# 12_MSM8916_POWER3.net
KiCad netlist of a schematic drawn in Altium Designer
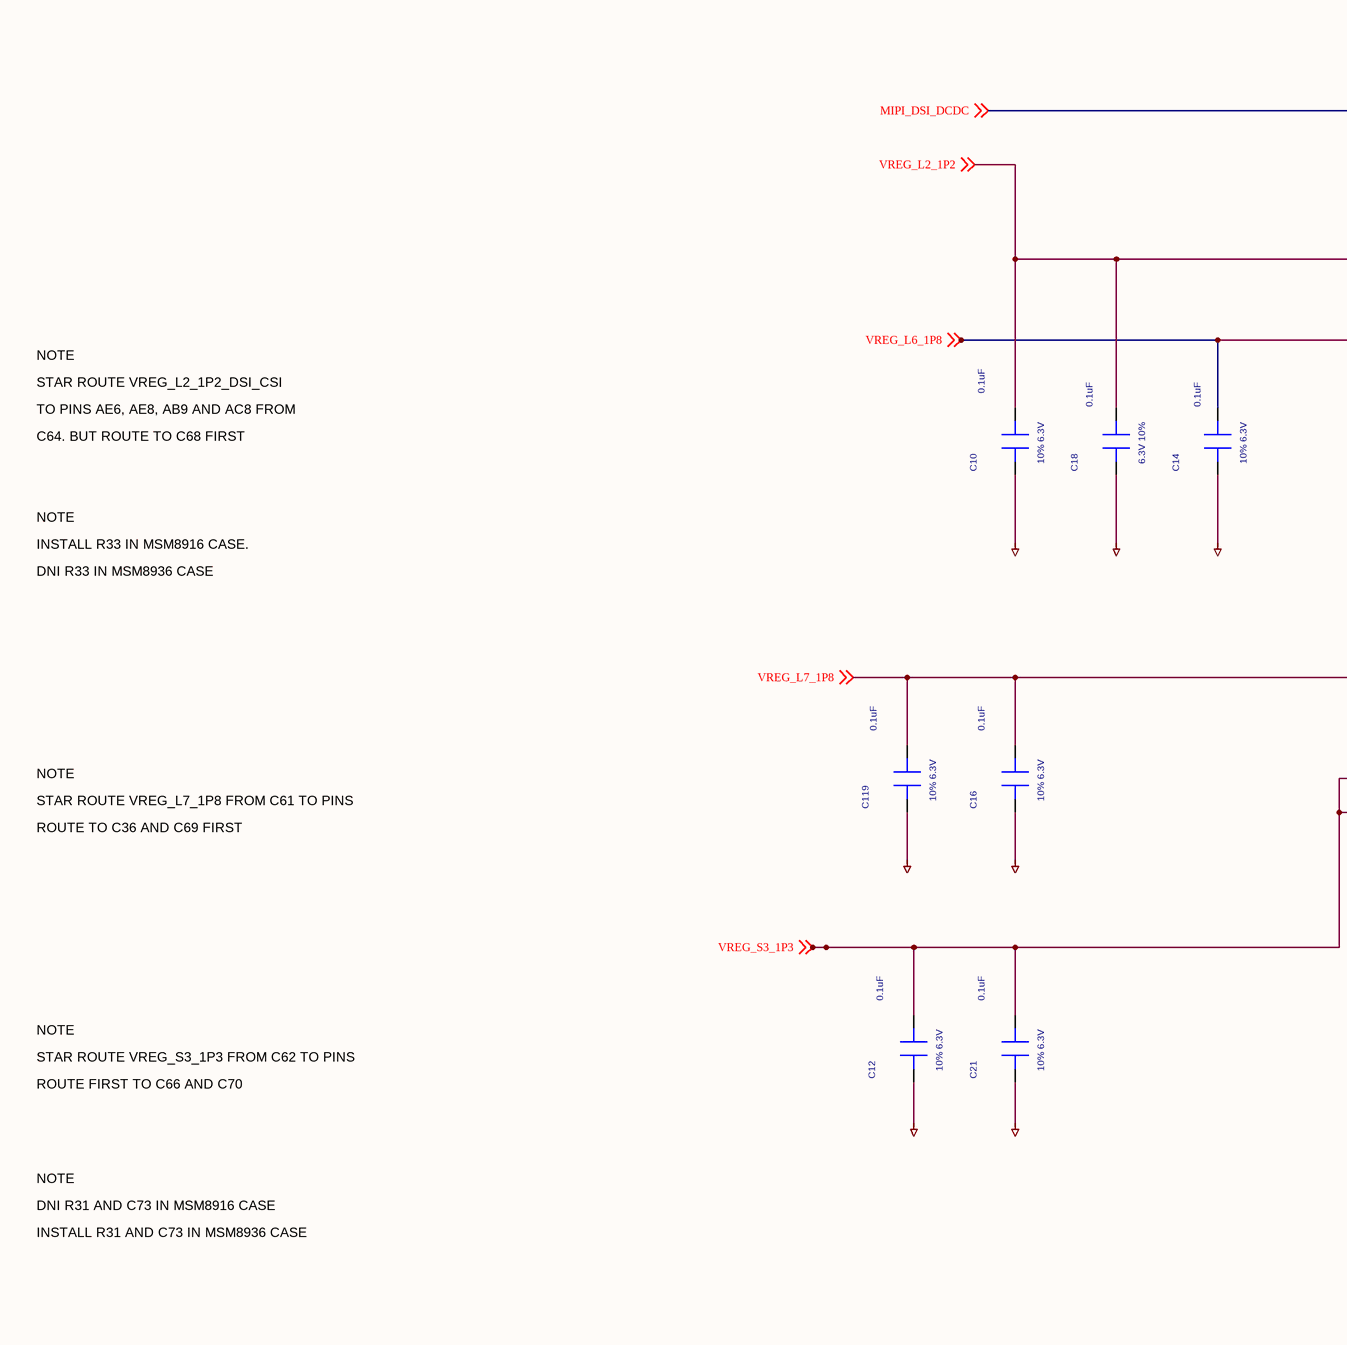
[diagram p0: 12 MSM8916_POWER3.SchDoc, top left]
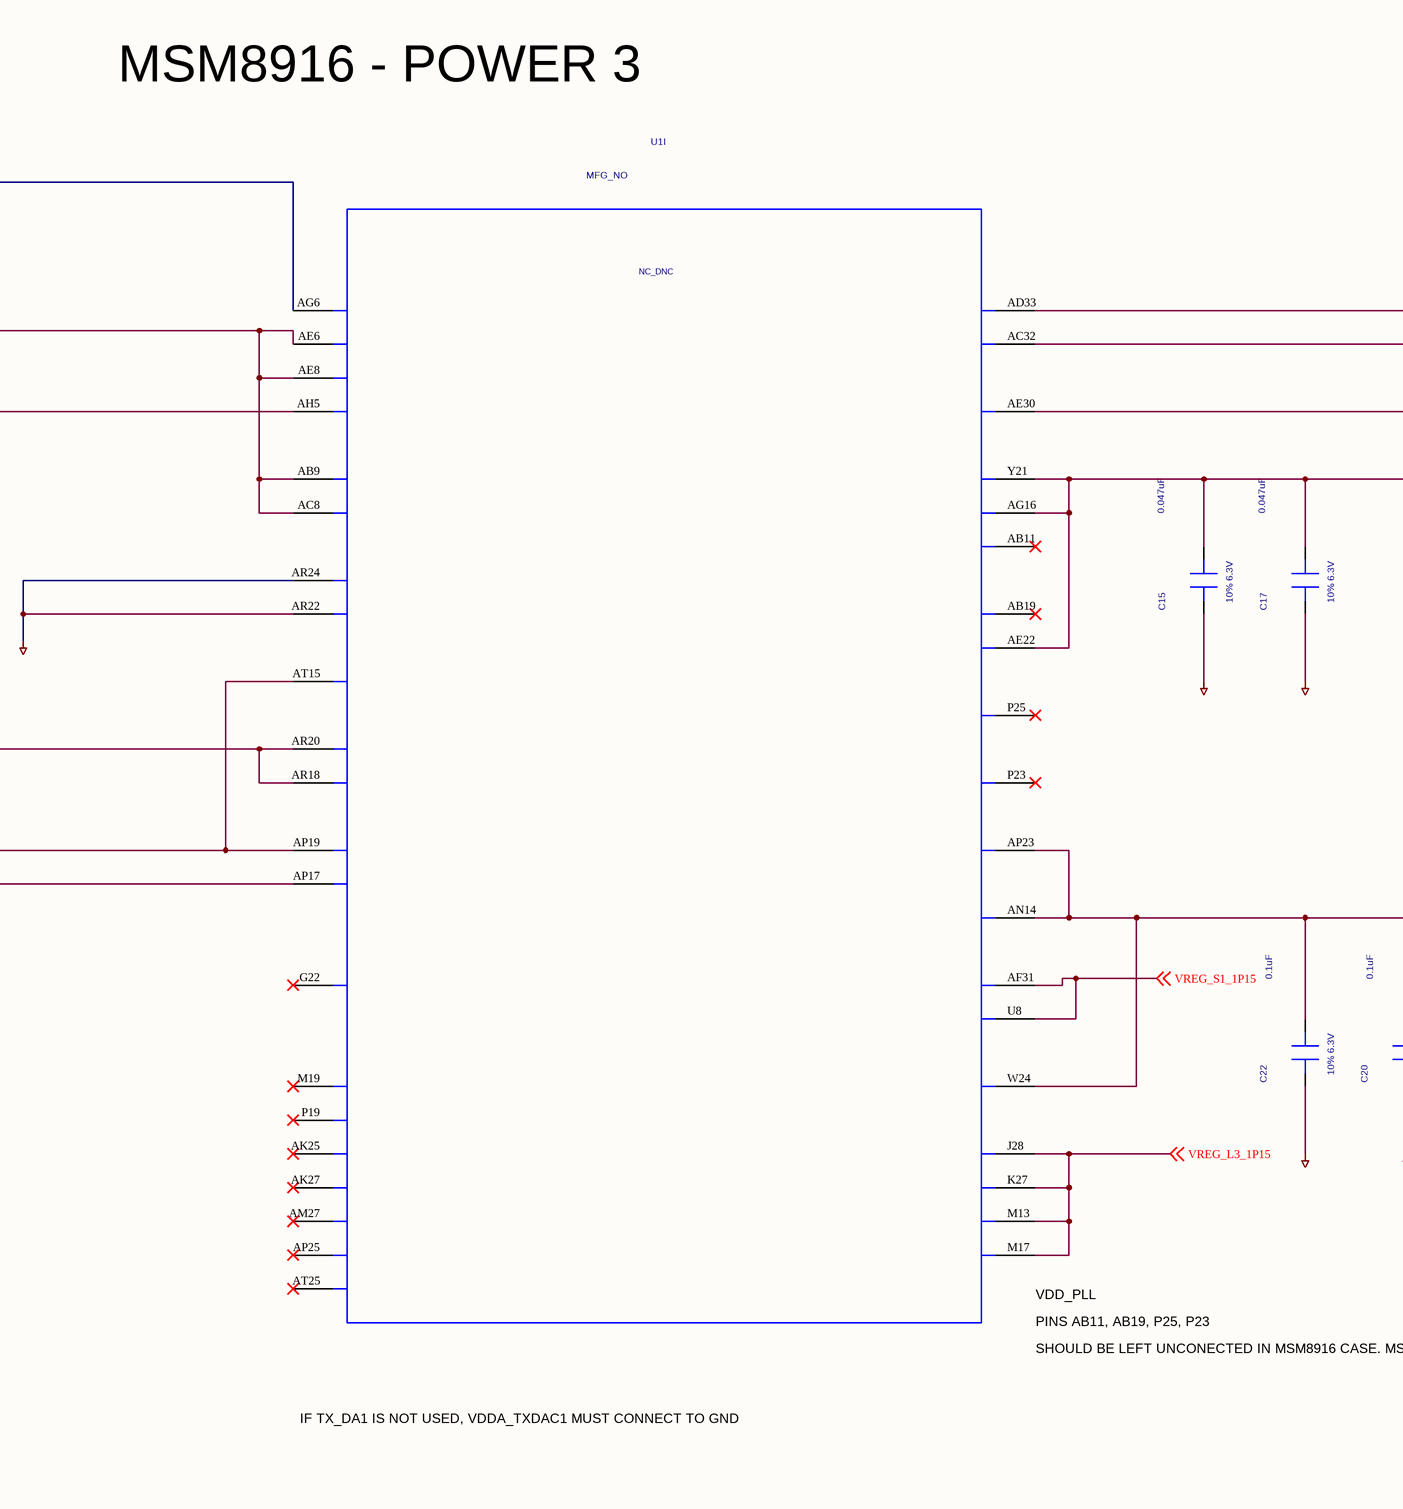
[diagram p1: 12 MSM8916_POWER3.SchDoc, top middle]
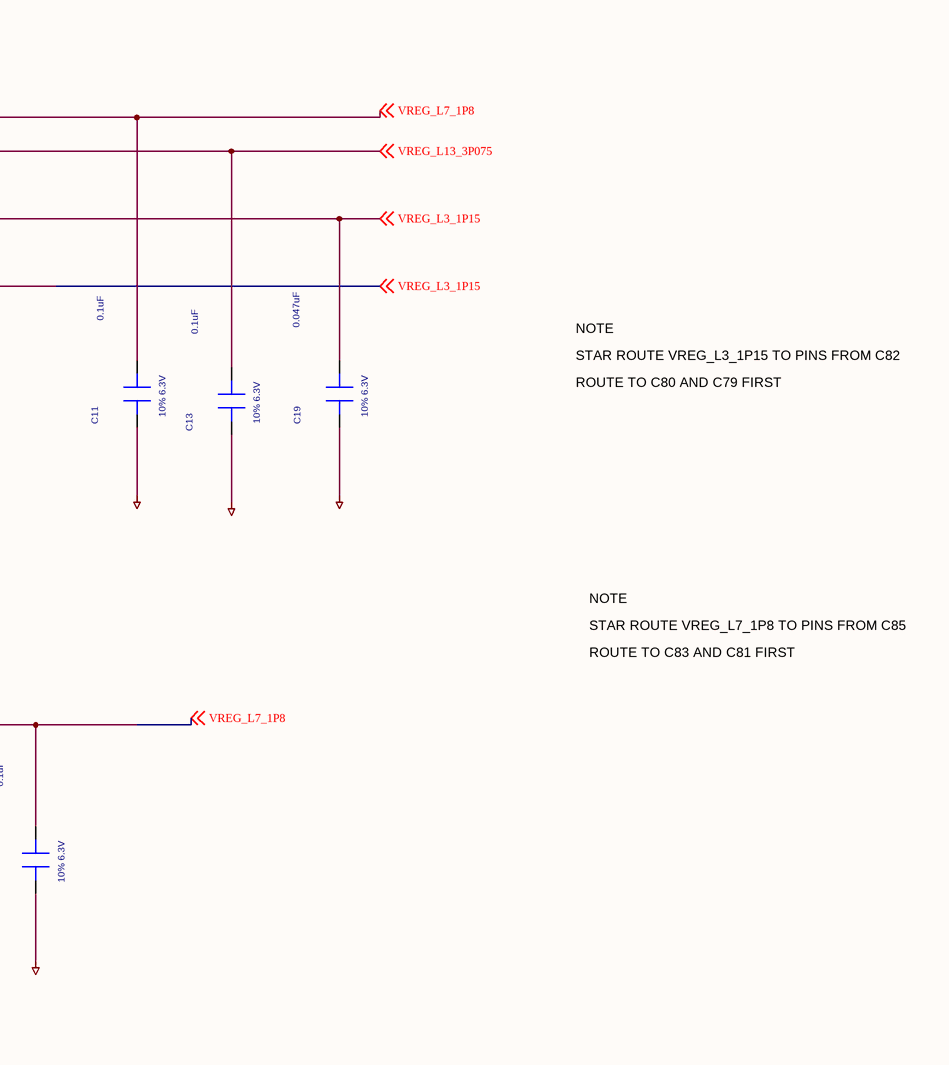
[diagram p2: 12 MSM8916_POWER3.SchDoc, top right]
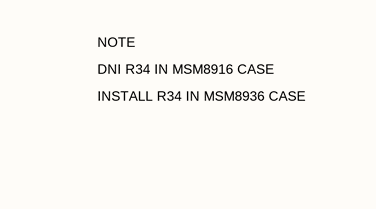
[diagram p3: 12 MSM8916_POWER3.SchDoc, bottom middle]
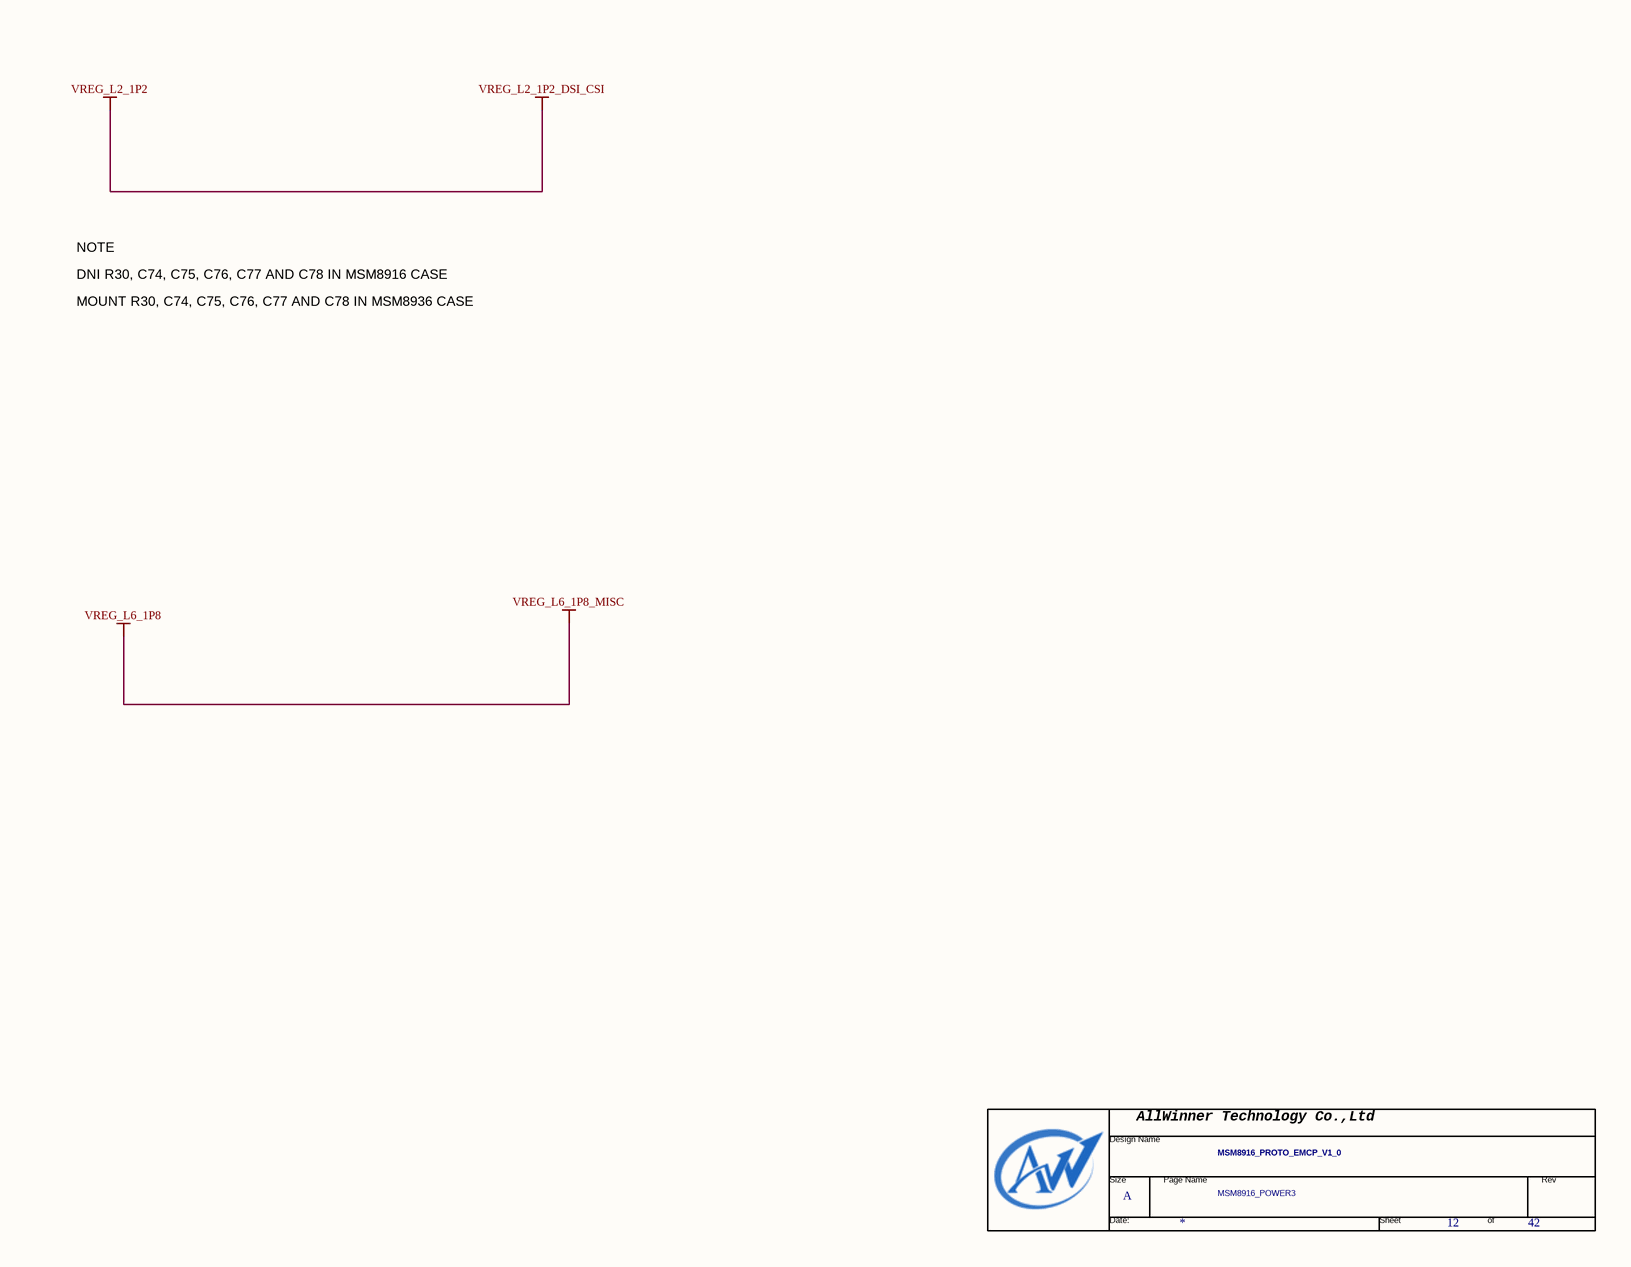
[diagram p4: 12 MSM8916_POWER3.SchDoc, bottom right]

(export (version "E")
  (design (tool "Eeschema 10.0.6"))
  (components
    (comp (ref "C10")
      (value "0.1uF")
      (footprint "c0402")
      (fields (field (name "TOLERANCE") "10% 6.3V") (field (name "PART_NUMBER") "MCN_NO"))
      (libsource (lib "MSM8916_DRAM_PMIC_REF_Library") (part "CAP#1"))
    )
    (comp (ref "C11")
      (value "0.1uF")
      (footprint "c0402")
      (fields (field (name "TOLERANCE") "10% 6.3V") (field (name "PART_NUMBER") "MCN_NO"))
      (libsource (lib "MSM8916_DRAM_PMIC_REF_Library") (part "CAP#1"))
    )
    (comp (ref "C12")
      (value "0.1uF")
      (footprint "c0402")
      (fields (field (name "TOLERANCE") "10% 6.3V") (field (name "PART_NUMBER") "MCN_NO"))
      (libsource (lib "MSM8916_DRAM_PMIC_REF_Library") (part "CAP#1"))
    )
    (comp (ref "C13")
      (value "0.1uF")
      (footprint "c0402")
      (fields (field (name "TOLERANCE") "10% 6.3V") (field (name "PART_NUMBER") "MCN_NO"))
      (libsource (lib "MSM8916_DRAM_PMIC_REF_Library") (part "CAP#1"))
    )
    (comp (ref "C14")
      (value "0.1uF")
      (footprint "c0402")
      (fields (field (name "TOLERANCE") "10% 6.3V") (field (name "PART_NUMBER") "MCN_NO"))
      (libsource (lib "MSM8916_DRAM_PMIC_REF_Library") (part "CAP#1"))
    )
    (comp (ref "C15")
      (value "0.047uF")
      (footprint "c0402")
      (fields (field (name "TOLERANCE") "10% 6.3V") (field (name "PART_NUMBER") "MCN_NO"))
      (libsource (lib "MSM8916_DRAM_PMIC_REF_Library") (part "CAP#1"))
    )
    (comp (ref "C16")
      (value "0.1uF")
      (footprint "c0402")
      (fields (field (name "TOLERANCE") "10% 6.3V") (field (name "PART_NUMBER") "MCN_NO"))
      (libsource (lib "MSM8916_DRAM_PMIC_REF_Library") (part "CAP#1"))
    )
    (comp (ref "C17")
      (value "0.047uF")
      (footprint "c0402")
      (fields (field (name "TOLERANCE") "10% 6.3V") (field (name "PART_NUMBER") "MCN_NO"))
      (libsource (lib "MSM8916_DRAM_PMIC_REF_Library") (part "CAP#1"))
    )
    (comp (ref "C18")
      (value "0.1uF")
      (footprint "c0402")
      (fields (field (name "TOLERANCE") "6.3V 10%") (field (name "PART_NUMBER") "MCN_NO"))
      (libsource (lib "MSM8916_DRAM_PMIC_REF_Library") (part "CAP#1"))
    )
    (comp (ref "C19")
      (value "0.047uF")
      (footprint "c0402")
      (fields (field (name "TOLERANCE") "10% 6.3V") (field (name "PART_NUMBER") "MCN_NO"))
      (libsource (lib "MSM8916_DRAM_PMIC_REF_Library") (part "CAP#1"))
    )
    (comp (ref "C20")
      (value "0.1uF")
      (footprint "c0402")
      (fields (field (name "TOLERANCE") "10% 6.3V") (field (name "PART_NUMBER") "MCN_NO"))
      (libsource (lib "MSM8916_DRAM_PMIC_REF_Library") (part "CAP#1"))
    )
    (comp (ref "C21")
      (value "0.1uF")
      (footprint "c0402")
      (fields (field (name "TOLERANCE") "10% 6.3V") (field (name "PART_NUMBER") "MCN_NO"))
      (libsource (lib "MSM8916_DRAM_PMIC_REF_Library") (part "CAP#1"))
    )
    (comp (ref "C22")
      (value "0.1uF")
      (footprint "c0402")
      (fields (field (name "TOLERANCE") "10% 6.3V") (field (name "PART_NUMBER") "MCN_NO"))
      (libsource (lib "MSM8916_DRAM_PMIC_REF_Library") (part "CAP#1"))
    )
    (comp (ref "C119")
      (value "0.1uF")
      (footprint "c0402")
      (fields (field (name "TOLERANCE") "10% 6.3V") (field (name "PART_NUMBER") "MCN_NO"))
      (libsource (lib "MSM8916_DRAM_PMIC_REF_Library") (part "CAP#1"))
    )
    (comp (ref "U1")
      (value "ASIC_MSM8936_760PIN")
      (footprint "MSM-8916-0-760NSP-TR-00-0")
      (fields
        (field (name "SYMNAME") "NC_DNC")
        (field (name "PART_NUMBER") "MCN_NO")
        (field (name "PART_ID") "MFG_NO")
      )
      (libsource (lib "MSM8916_DRAM_PMIC_REF_Library") (part "ASIC_MSM8936_760PIN"))
    )
  )
  (nets
    (net (code "1") (name "DGND") (class "Default")
      (node (ref "C10") (pin "1") (pinfunction "POS_1") (pintype "bidirectional"))
      (node (ref "C11") (pin "1") (pinfunction "POS_1") (pintype "bidirectional"))
      (node (ref "C119") (pin "1") (pinfunction "POS_1") (pintype "bidirectional"))
      (node (ref "C12") (pin "1") (pinfunction "POS_1") (pintype "bidirectional"))
      (node (ref "C13") (pin "1") (pinfunction "POS_1") (pintype "bidirectional"))
      (node (ref "C14") (pin "1") (pinfunction "POS_1") (pintype "bidirectional"))
      (node (ref "C15") (pin "1") (pinfunction "POS_1") (pintype "bidirectional"))
      (node (ref "C16") (pin "1") (pinfunction "POS_1") (pintype "bidirectional"))
      (node (ref "C17") (pin "1") (pinfunction "POS_1") (pintype "bidirectional"))
      (node (ref "C18") (pin "1") (pinfunction "POS_1") (pintype "bidirectional"))
      (node (ref "C19") (pin "1") (pinfunction "POS_1") (pintype "bidirectional"))
      (node (ref "C20") (pin "1") (pinfunction "POS_1") (pintype "bidirectional"))
      (node (ref "C21") (pin "1") (pinfunction "POS_1") (pintype "bidirectional"))
      (node (ref "C22") (pin "1") (pinfunction "POS_1") (pintype "bidirectional"))
      (node (ref "U1") (pin "AR22") (pinfunction "VDDA_TXDAC1_AR22") (pintype "power_in"))
      (node (ref "U1") (pin "AR24") (pinfunction "VDDA_TXDAC0_AR24") (pintype "power_in"))
    )
    (net (code "2") (name "MIPI_DSI_DCDC") (class "Default")
      (node (ref "U1") (pin "AG6") (pinfunction "VDDA_0P4_MIPI_DSI_AG6") (pintype "power_in"))
    )
    (net (code "3") (name "VREG_L2_1P2") (class "Default")
      (node (ref "C10") (pin "2") (pinfunction "NEG_2") (pintype "bidirectional"))
      (node (ref "C18") (pin "2") (pinfunction "NEG_2") (pintype "bidirectional"))
      (node (ref "U1") (pin "AB9") (pinfunction "VDDA_MIPI_CSI_1_AB9") (pintype "power_in"))
      (node (ref "U1") (pin "AC8") (pinfunction "VDDA_MIPI_CSI_2_AC8") (pintype "power_in"))
      (node (ref "U1") (pin "AE6") (pinfunction "VDDA_1P2_MIPI_DSI_1_AE6") (pintype "power_in"))
      (node (ref "U1") (pin "AE8") (pinfunction "VDDA_1P2_MIPI_DSI_2_AE8") (pintype "power_in"))
    )
    (net (code "4") (name "VREG_L3_1P15") (class "Default")
      (node (ref "C15") (pin "2") (pinfunction "NEG_2") (pintype "bidirectional"))
      (node (ref "C17") (pin "2") (pinfunction "NEG_2") (pintype "bidirectional"))
      (node (ref "C19") (pin "2") (pinfunction "NEG_2") (pintype "bidirectional"))
      (node (ref "U1") (pin "AE22") (pinfunction "VDD_SR_MPLL2_GPLL1_AE22") (pintype "power_in"))
      (node (ref "U1") (pin "AE30") (pinfunction "USB2_HS_DVDD_AE30") (pintype "power_in"))
      (node (ref "U1") (pin "AG16") (pinfunction "VDD_SR_GPLL3_AG16") (pintype "power_in"))
      (node (ref "U1") (pin "J28") (pinfunction "VDDA_CDC_EBI0_CA_D0_D1_D2_D3_1_J28") (pintype "power_in"))
      (node (ref "U1") (pin "K27") (pinfunction "VDDA_CDC_EBI0_CA_D0_D1_D2_D3_2_K27") (pintype "power_in"))
      (node (ref "U1") (pin "M13") (pinfunction "VDDA_CDC_EBI0_CA_D0_D1_D2_D3_3_M13") (pintype "power_in"))
      (node (ref "U1") (pin "M17") (pinfunction "VDDA_CDC_EBI0_CA_D0_D1_D2_D3_4_M17") (pintype "power_in"))
      (node (ref "U1") (pin "Y21") (pinfunction "VDD_SR_GPLL0_GPLL2_Y21") (pintype "power_in"))
    )
    (net (code "5") (name "VREG_L6_1P8") (class "Default")
      (node (ref "C14") (pin "2") (pinfunction "NEG_2") (pintype "bidirectional"))
      (node (ref "U1") (pin "AH5") (pinfunction "VDDA_MIPI_DSI_PLL_AH5") (pintype "power_in"))
    )
    (net (code "6") (name "VREG_L7_1P8") (class "Default")
      (node (ref "C11") (pin "2") (pinfunction "NEG_2") (pintype "bidirectional"))
      (node (ref "C119") (pin "2") (pinfunction "NEG_2") (pintype "bidirectional"))
      (node (ref "C16") (pin "2") (pinfunction "NEG_2") (pintype "bidirectional"))
      (node (ref "C20") (pin "2") (pinfunction "NEG_2") (pintype "bidirectional"))
      (node (ref "C22") (pin "2") (pinfunction "NEG_2") (pintype "bidirectional"))
      (node (ref "U1") (pin "AD33") (pinfunction "USB2_HS_VDDA_1P8_AD33") (pintype "power_in"))
      (node (ref "U1") (pin "AN14") (pinfunction "VDD_SR2_PRONTO_PLL_AN14") (pintype "power_in"))
      (node (ref "U1") (pin "AP23") (pinfunction "VDD_SR2_MODEM_PLL1_AP23") (pintype "power_in"))
      (node (ref "U1") (pin "AR18") (pinfunction "VDDAH_BBRX_CH2_AR18") (pintype "power_in"))
      (node (ref "U1") (pin "AR20") (pinfunction "VDDAH_BBRX_CH0_1_AR20") (pintype "power_in"))
      (node (ref "U1") (pin "W24") (pinfunction "VDD_HF_APPS_PLL_W24") (pintype "power_in"))
    )
    (net (code "7") (name "VREG_L13_3P075") (class "Default")
      (node (ref "C13") (pin "2") (pinfunction "NEG_2") (pintype "bidirectional"))
      (node (ref "U1") (pin "AC32") (pinfunction "USB2_HS_VDDA_3P3_AC32") (pintype "power_in"))
    )
    (net (code "8") (name "VREG_S1_1P15") (class "Default")
      (node (ref "U1") (pin "AF31") (pinfunction "VDD_CDC_SDC1_AF31") (pintype "power_in"))
      (node (ref "U1") (pin "U8") (pinfunction "VDD_CDC_SDC2_U8") (pintype "power_in"))
    )
    (net (code "9") (name "VREG_S3_1P3") (class "Default")
      (node (ref "C12") (pin "2") (pinfunction "NEG_2") (pintype "bidirectional"))
      (node (ref "C21") (pin "2") (pinfunction "NEG_2") (pintype "bidirectional"))
      (node (ref "U1") (pin "AP17") (pinfunction "VDDAL_BBRX_CH2_GPSADC_AP17") (pintype "power_in"))
      (node (ref "U1") (pin "AP19") (pinfunction "VDDAL_BBRX_CH0_1_AP19") (pintype "power_in"))
      (node (ref "U1") (pin "AT15") (pinfunction "VDDA_WLAN_AT15") (pintype "power_in"))
    )
    (net (code "10") (name "unconnected-(U1I-VDDA_PLL_1P8-PadG22)") (class "Default")
      (node (ref "U1") (pin "G22") (pinfunction "VDDA_PLL_1P8_G22") (pintype "power_in+no_connect"))
    )
    (net (code "11") (name "unconnected-(U1I-VDD_MSS_1-PadM19)") (class "Default")
      (node (ref "U1") (pin "M19") (pinfunction "VDD_MSS_1_M19") (pintype "power_in+no_connect"))
    )
    (net (code "12") (name "unconnected-(U1I-VDD_MSS_2-PadP19)") (class "Default")
      (node (ref "U1") (pin "P19") (pinfunction "VDD_MSS_2_P19") (pintype "power_in+no_connect"))
    )
    (net (code "13") (name "unconnected-(U1I-VDD_MSS_3-PadAK25)") (class "Default")
      (node (ref "U1") (pin "AK25") (pinfunction "VDD_MSS_3_AK25") (pintype "power_in+no_connect"))
    )
    (net (code "14") (name "unconnected-(U1I-VDD_MSS_4-PadAK27)") (class "Default")
      (node (ref "U1") (pin "AK27") (pinfunction "VDD_MSS_4_AK27") (pintype "power_in+no_connect"))
    )
    (net (code "15") (name "unconnected-(U1I-VDD_MSS_5-PadAM27)") (class "Default")
      (node (ref "U1") (pin "AM27") (pinfunction "VDD_MSS_5_AM27") (pintype "power_in+no_connect"))
    )
    (net (code "16") (name "unconnected-(U1I-VDD_MSS_6-PadAP25)") (class "Default")
      (node (ref "U1") (pin "AP25") (pinfunction "VDD_MSS_6_AP25") (pintype "power_in+no_connect"))
    )
    (net (code "17") (name "unconnected-(U1I-VDD_MSS_7-PadAT25)") (class "Default")
      (node (ref "U1") (pin "AT25") (pinfunction "VDD_MSS_7_AT25") (pintype "power_in+no_connect"))
    )
    (net (code "18") (name "unconnected-(U1I-VDD_SR2_APPS_PLL-PadP25)") (class "Default")
      (node (ref "U1") (pin "P25") (pinfunction "VDD_SR2_APPS_PLL_P25") (pintype "power_in+no_connect"))
    )
    (net (code "19") (name "unconnected-(U1I-VDD_SR2_BIMC_GPLL5-PadP23)") (class "Default")
      (node (ref "U1") (pin "P23") (pinfunction "VDD_SR2_BIMC_GPLL5_P23") (pintype "power_in+no_connect"))
    )
    (net (code "20") (name "unconnected-(U1I-VDD_SR_GPLL4-PadAB11)") (class "Default")
      (node (ref "U1") (pin "AB11") (pinfunction "VDD_SR_GPLL4_AB11") (pintype "power_in+no_connect"))
    )
    (net (code "21") (name "unconnected-(U1I-VDD_SR_MPLL0_GPLL6-PadAB19)") (class "Default")
      (node (ref "U1") (pin "AB19") (pinfunction "VDD_SR_MPLL0_GPLL6_AB19") (pintype "power_in+no_connect"))
    )
  )
)
